# Ada_-_small_square_incomplete.net
KiCad netlist of a schematic drawn in EasyEDA Pro
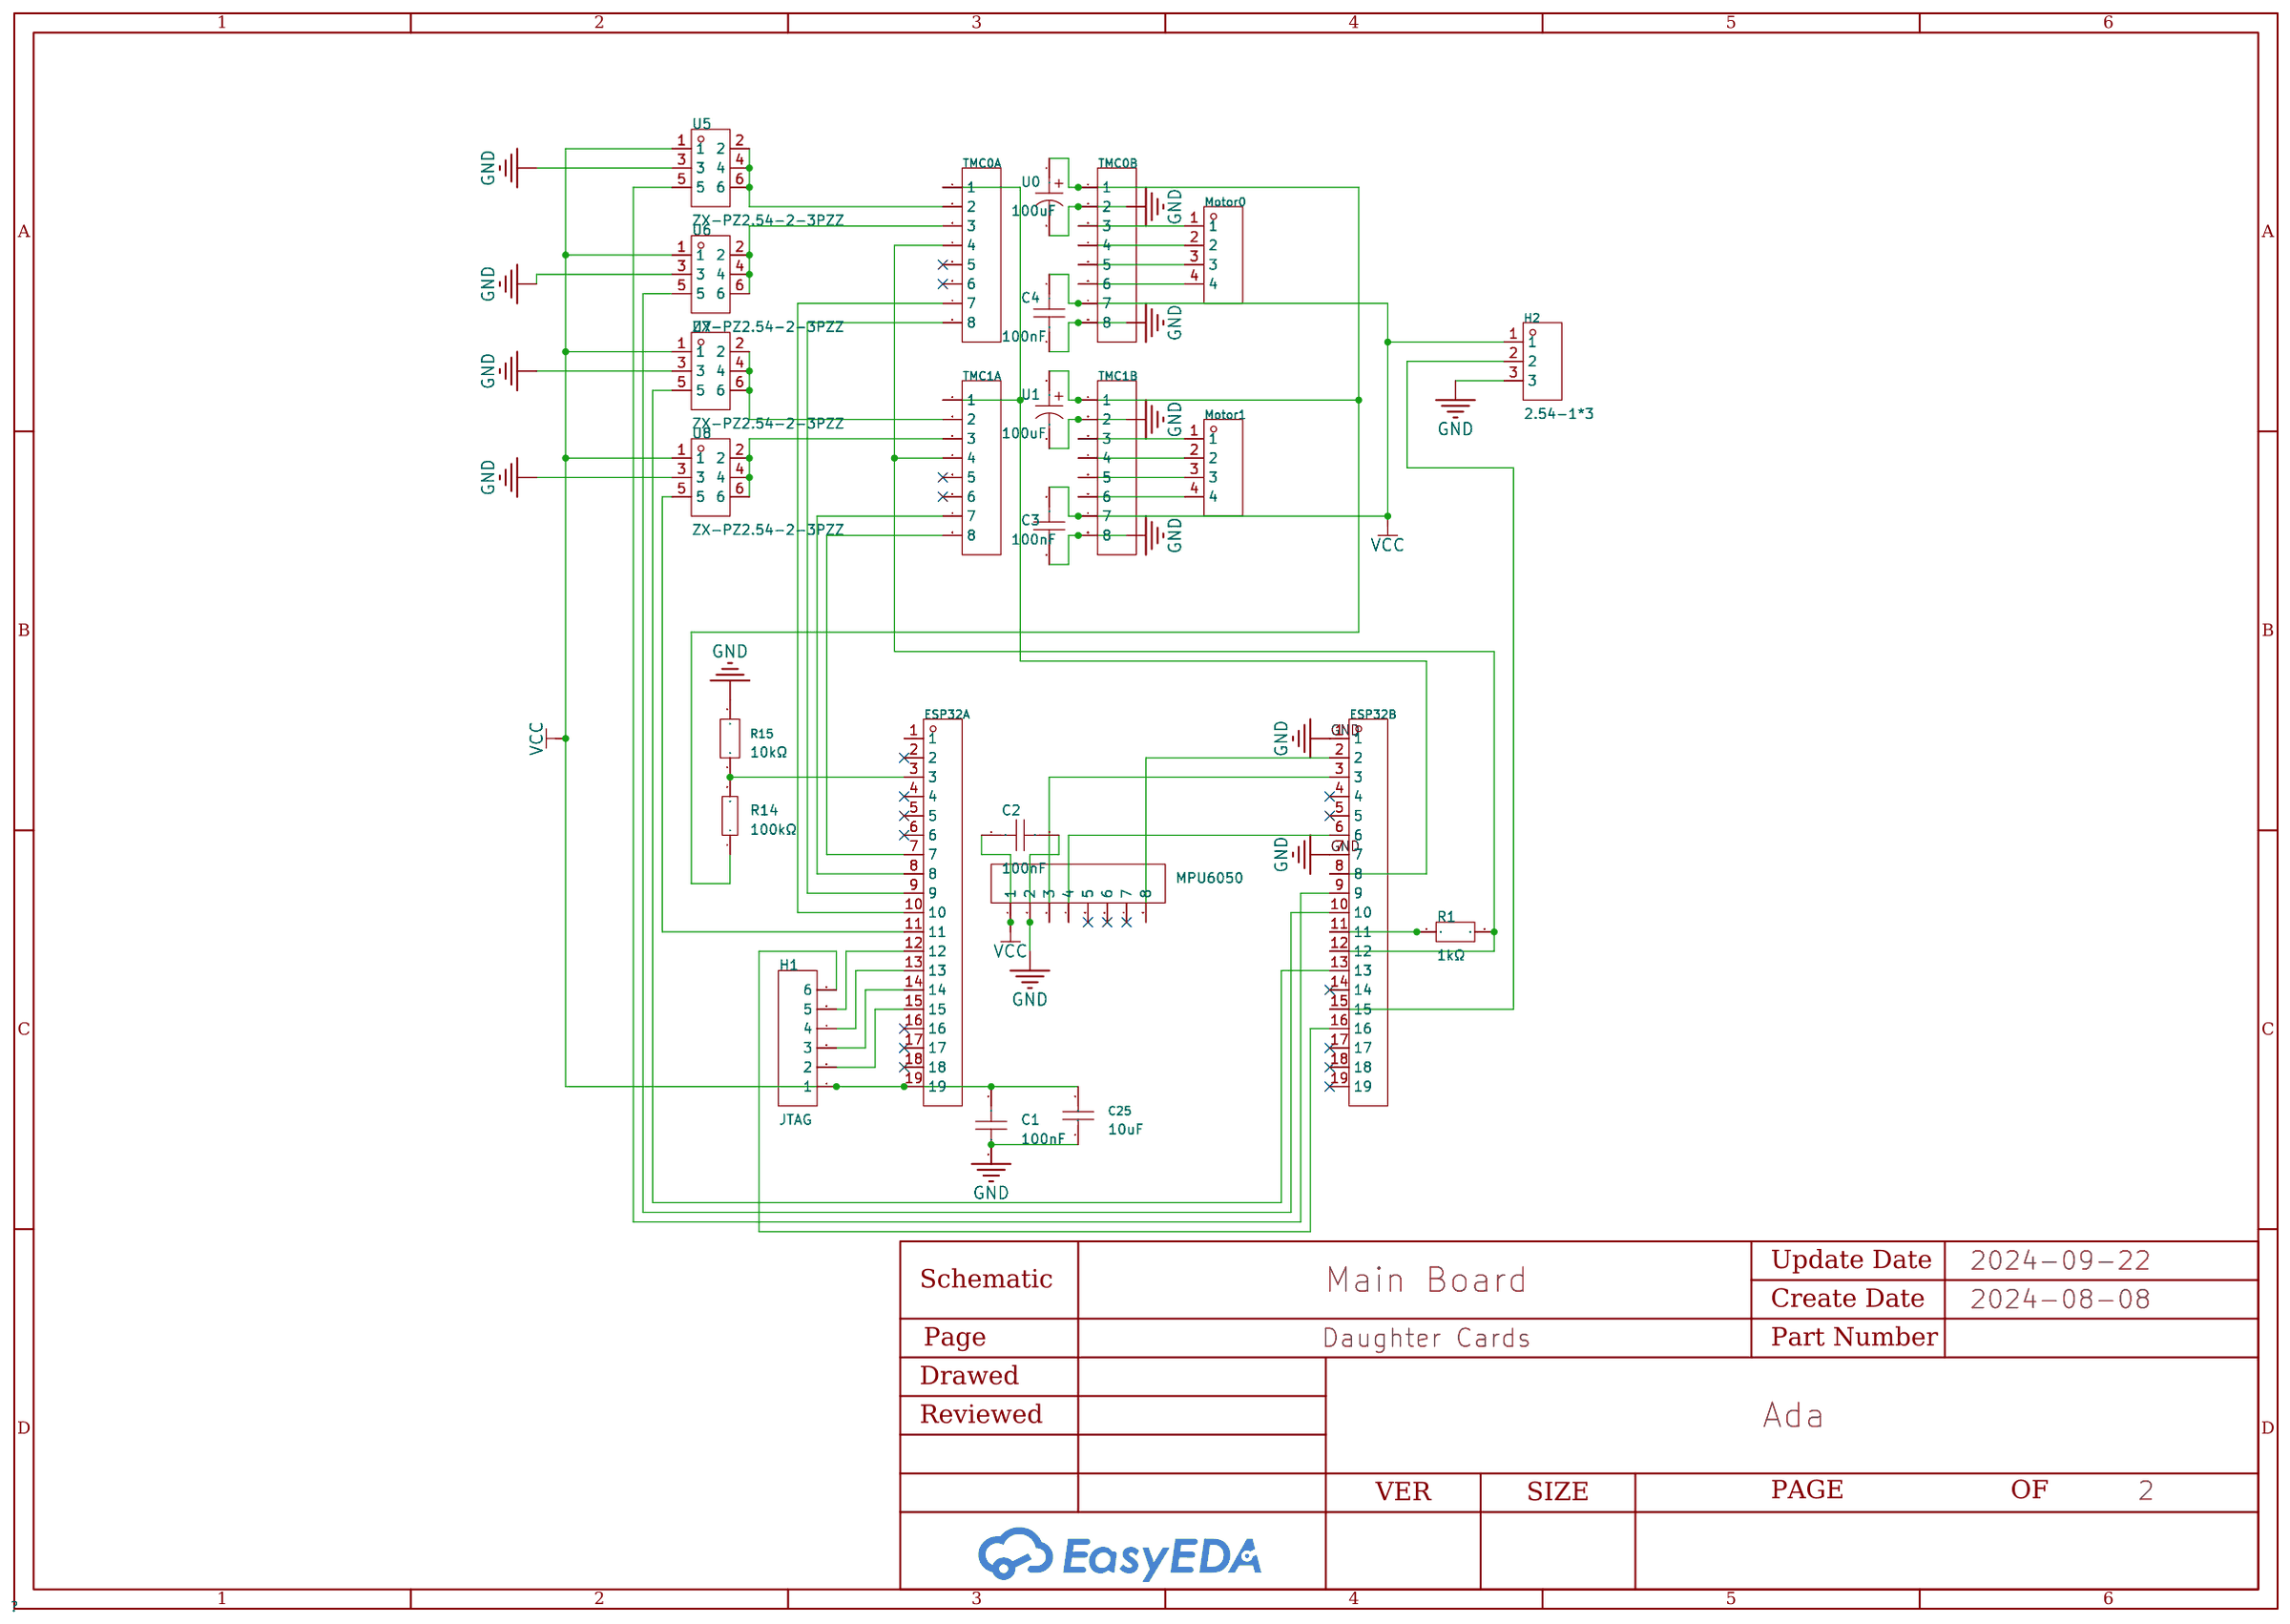
[diagram p0: Daughter Cards]
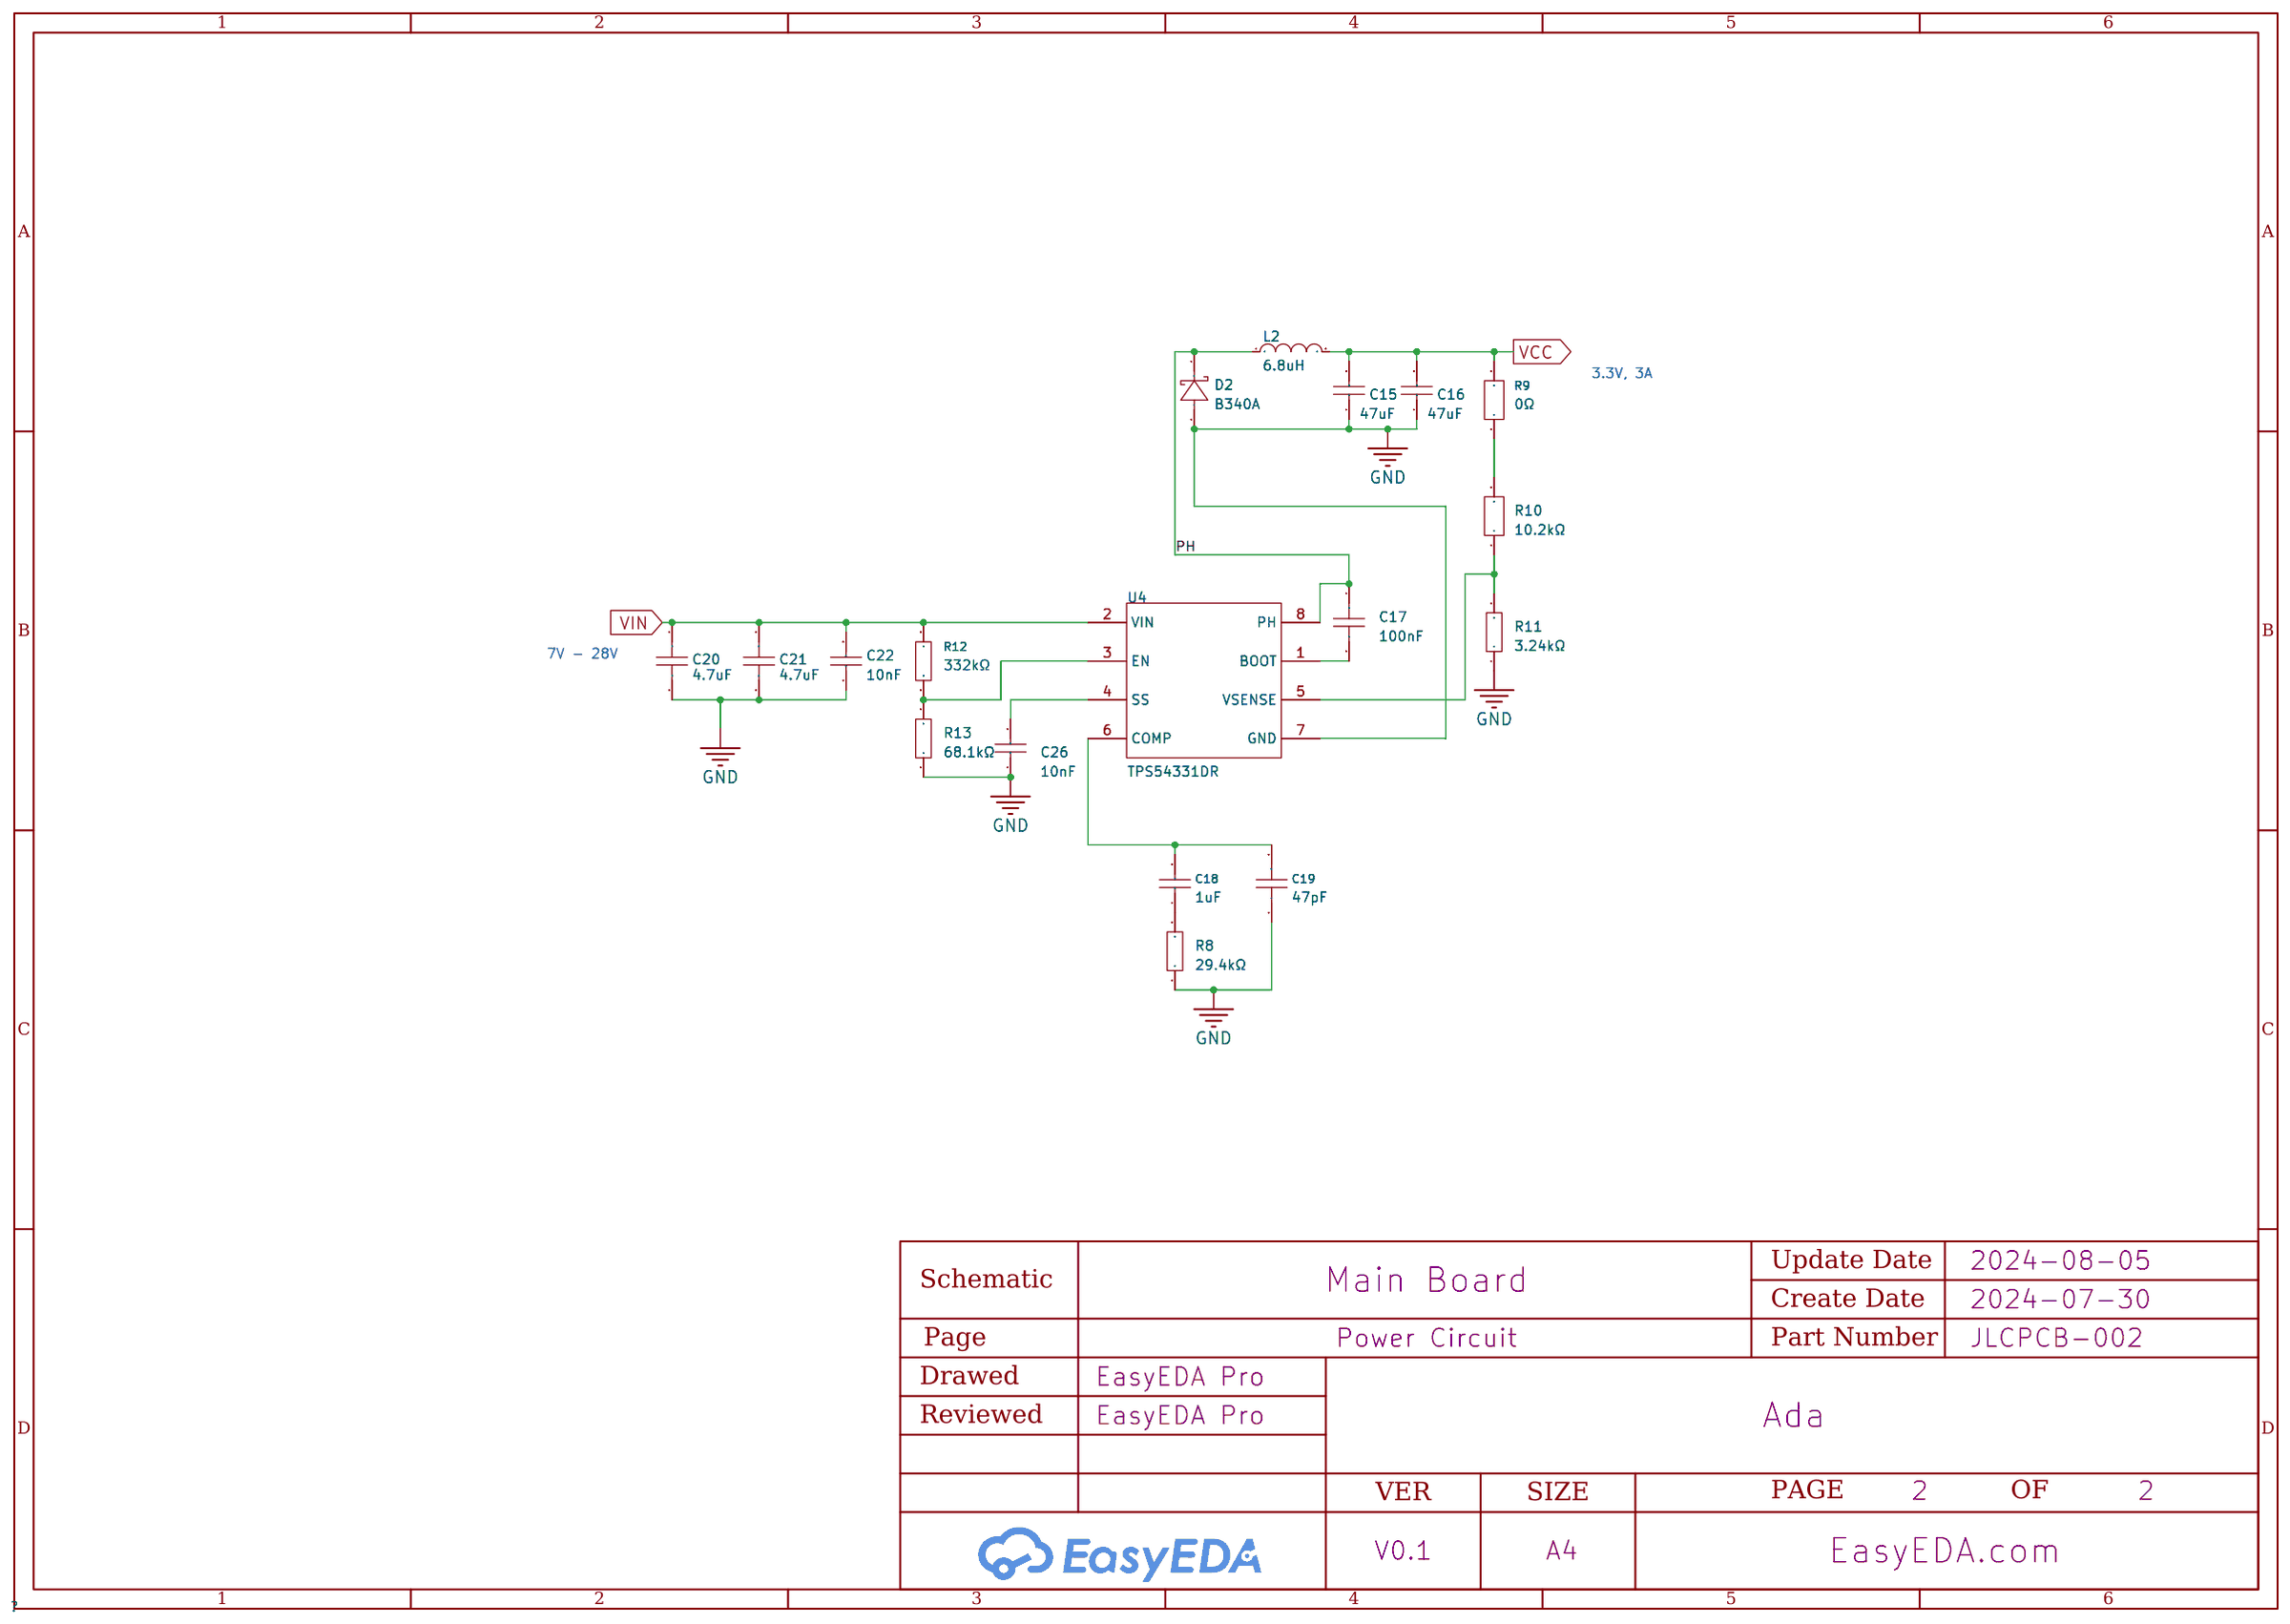
[diagram p1: Power Circuit]

(export (version "E")
  (design (tool "Eeschema 10.0.6"))
  (components
    (comp (ref "C1")
      (value "100nF")
      (footprint "easyedapro:C0201")
      (fields
        (field (name "Manufacturer Part") "CL03A104KQ3NNNC")
        (field (name "Manufacturer") "SAMSUNG(三星)")
      )
      (libsource (lib "easyedapro") (part "CL03A104KQ3NNNC"))
    )
    (comp (ref "C2")
      (value "100nF")
      (footprint "easyedapro:C0201")
      (fields
        (field (name "Manufacturer Part") "CL03A104KQ3NNNC")
        (field (name "Manufacturer") "SAMSUNG(三星)")
      )
      (libsource (lib "easyedapro") (part "CL03A104KQ3NNNC"))
    )
    (comp (ref "C3")
      (value "100nF")
      (footprint "easyedapro:C0201")
      (fields
        (field (name "Manufacturer Part") "CL03A104KQ3NNNC")
        (field (name "Manufacturer") "SAMSUNG(三星)")
      )
      (libsource (lib "easyedapro") (part "CL03A104KQ3NNNC"))
    )
    (comp (ref "C4")
      (value "100nF")
      (footprint "easyedapro:C0201")
      (fields
        (field (name "Manufacturer Part") "CL03A104KQ3NNNC")
        (field (name "Manufacturer") "SAMSUNG(三星)")
      )
      (libsource (lib "easyedapro") (part "CL03A104KQ3NNNC"))
    )
    (comp (ref "C25")
      (value "10uF")
      (footprint "easyedapro:C0402")
      (fields
        (field (name "Manufacturer Part") "CL05A106MQ5NUNC")
        (field (name "Manufacturer") "SAMSUNG(三星)")
      )
      (libsource (lib "easyedapro") (part "CL05A106MQ5NUNC"))
    )
    (comp (ref "ESP32A")
      (value "ESP32")
      (footprint "easyedapro:HDR-TH_19P-P2.54-V-F")
      (fields (field (name "Manufacturer Part") "2.54-1*19P母") (field (name "Manufacturer") "BOOMELE(博穆精密)"))
      (libsource (lib "easyedapro") (part "2.54-1*19P母"))
    )
    (comp (ref "ESP32B")
      (value "2.54-1*19P母")
      (footprint "easyedapro:HDR-TH_19P-P2.54-V-F")
      (fields (field (name "Manufacturer") "BOOMELE(博穆精密)"))
      (libsource (lib "easyedapro") (part "2.54-1*19P母"))
    )
    (comp (ref "H1")
      (value "JTAG")
      (footprint "easyedapro:HDR-TH_6P-P2.54-V-M-1")
      (fields (field (name "Manufacturer Part") "2.54-1x6P直针") (field (name "Manufacturer") "BOOMELE(博穆精密)"))
      (libsource (lib "easyedapro") (part "Header-Male-2.54_1x6"))
    )
    (comp (ref "H2")
      (value "2.54-1*3")
      (footprint "easyedapro:HDR-TH_3P-P2.54-V-M-1")
      (description "Pin Structure:1x3P Pitch:2.54mm Number of Rows:Plugin Number of Pins:3P Contact Plating:Gold")
      (fields (field (name "Manufacturer") "ZHOURI(洲日)"))
      (libsource (lib "easyedapro") (part "2.54-1*3"))
    )
    (comp (ref "Motor0")
      (value "Motor 0")
      (footprint "easyedapro:HDR-TH_4P-P2.54-V-M")
      (fields (field (name "Manufacturer Part") "PZ254V-11-04P") (field (name "Manufacturer") "XFCN(兴飞)"))
      (libsource (lib "easyedapro") (part "PZ254V-11-04P_C2691448"))
    )
    (comp (ref "Motor1")
      (value "Motor 1")
      (footprint "easyedapro:HDR-TH_4P-P2.54-V-M")
      (fields (field (name "Manufacturer Part") "PZ254V-11-04P") (field (name "Manufacturer") "XFCN(兴飞)"))
      (libsource (lib "easyedapro") (part "PZ254V-11-04P_C2691448"))
    )
    (comp (ref "MPU6050")
      (value "MPU6050")
      (footprint "easyedapro:HDR-TH_8P-P2.54-V-F-1")
      (fields (field (name "Manufacturer Part") "2.54-1*8P母环保") (field (name "Manufacturer") "BOOMELE(博穆精密)"))
      (libsource (lib "easyedapro") (part "Header-Female-2.54_1x8"))
    )
    (comp (ref "R1")
      (value "1kΩ")
      (footprint "easyedapro:R0603")
      (fields (field (name "Manufacturer Part") "FCR0603F1K") (field (name "Manufacturer") "VO(翔胜)"))
      (libsource (lib "easyedapro") (part "FCR0603F1K"))
    )
    (comp (ref "R14")
      (value "100kΩ")
      (footprint "easyedapro:R0201")
      (fields
        (field (name "Manufacturer Part") "0201WMF1003TEE")
        (field (name "Manufacturer") "UNI-ROYAL(厚声)")
      )
      (libsource (lib "easyedapro") (part "0201WMF1003TEE"))
    )
    (comp (ref "R15")
      (value "10kΩ")
      (footprint "easyedapro:R0201")
      (fields
        (field (name "Manufacturer Part") "0201WMF1002TEE")
        (field (name "Manufacturer") "UNI-ROYAL(厚声)")
      )
      (libsource (lib "easyedapro") (part "0201WMF1002TEE"))
    )
    (comp (ref "TMC0A")
      (value "TMC0A")
      (footprint "easyedapro:HDR-TH_8P-P2.54-V-F-1")
      (fields (field (name "Manufacturer Part") "2.54-1*8P母环保") (field (name "Manufacturer") "BOOMELE(博穆精密)"))
      (libsource (lib "easyedapro") (part "Header-Female-2.54_1x8"))
    )
    (comp (ref "TMC0B")
      (value "2.54-1*8P母环保")
      (footprint "easyedapro:HDR-TH_8P-P2.54-V-F-1")
      (fields (field (name "Manufacturer") "BOOMELE(博穆精密)"))
      (libsource (lib "easyedapro") (part "Header-Female-2.54_1x8"))
    )
    (comp (ref "TMC1A")
      (value "TMC2209")
      (footprint "easyedapro:HDR-TH_8P-P2.54-V-F-1")
      (fields (field (name "Manufacturer Part") "2.54-1*8P母环保") (field (name "Manufacturer") "BOOMELE(博穆精密)"))
      (libsource (lib "easyedapro") (part "Header-Female-2.54_1x8"))
    )
    (comp (ref "TMC1B")
      (value "2.54-1*8P母环保")
      (footprint "easyedapro:HDR-TH_8P-P2.54-V-F-1")
      (fields (field (name "Manufacturer") "BOOMELE(博穆精密)"))
      (libsource (lib "easyedapro") (part "Header-Female-2.54_1x8"))
    )
    (comp (ref "U0")
      (value "100uF")
      (footprint "easyedapro:CAP-TH_BD6.3-P2.50-D0.5-FD")
      (fields (field (name "Manufacturer Part") "03EC0728") (field (name "Manufacturer") "KNSCHA(科尼盛)"))
      (libsource (lib "easyedapro") (part "03EC0728"))
    )
    (comp (ref "U1")
      (value "100uF")
      (footprint "easyedapro:CAP-TH_BD6.3-P2.50-D0.5-FD")
      (fields (field (name "Manufacturer Part") "03EC0728") (field (name "Manufacturer") "KNSCHA(科尼盛)"))
      (libsource (lib "easyedapro") (part "03EC0728"))
    )
    (comp (ref "U5")
      (value "ZX-PZ2.54-2-3PZZ")
      (footprint "easyedapro:HDR-TH_6P-P2.54-V-M-R2-C3-S2.54-1")
      (fields (field (name "Manufacturer") "Megastar(兆星)"))
      (libsource (lib "easyedapro") (part "ZX-PZ2.54-2-3PZZ"))
    )
    (comp (ref "U6")
      (value "ZX-PZ2.54-2-3PZZ")
      (footprint "easyedapro:HDR-TH_6P-P2.54-V-M-R2-C3-S2.54-1")
      (fields (field (name "Manufacturer") "Megastar(兆星)"))
      (libsource (lib "easyedapro") (part "ZX-PZ2.54-2-3PZZ"))
    )
    (comp (ref "U7")
      (value "ZX-PZ2.54-2-3PZZ")
      (footprint "easyedapro:HDR-TH_6P-P2.54-V-M-R2-C3-S2.54-1")
      (fields (field (name "Manufacturer") "Megastar(兆星)"))
      (libsource (lib "easyedapro") (part "ZX-PZ2.54-2-3PZZ"))
    )
    (comp (ref "U8")
      (value "ZX-PZ2.54-2-3PZZ")
      (footprint "easyedapro:HDR-TH_6P-P2.54-V-M-R2-C3-S2.54-1")
      (fields (field (name "Manufacturer") "Megastar(兆星)"))
      (libsource (lib "easyedapro") (part "ZX-PZ2.54-2-3PZZ"))
    )
    (comp (ref "C15")
      (value "47uF")
      (footprint "easyedapro:C0805")
      (fields
        (field (name "Manufacturer Part") "CL21A476MQYNNNE")
        (field (name "Manufacturer") "SAMSUNG(三星)")
      )
      (libsource (lib "easyedapro") (part "CL21A476MQYNNNE"))
    )
    (comp (ref "C16")
      (value "47uF")
      (footprint "easyedapro:C0805")
      (fields
        (field (name "Manufacturer Part") "CL21A476MQYNNNE")
        (field (name "Manufacturer") "SAMSUNG(三星)")
      )
      (libsource (lib "easyedapro") (part "CL21A476MQYNNNE"))
    )
    (comp (ref "C17")
      (value "100nF")
      (footprint "easyedapro:C0201")
      (fields
        (field (name "Manufacturer Part") "CL03A104KQ3NNNC")
        (field (name "Manufacturer") "SAMSUNG(三星)")
      )
      (libsource (lib "easyedapro") (part "CL03A104KQ3NNNC"))
    )
    (comp (ref "C18")
      (value "1uF")
      (footprint "easyedapro:C0402")
      (fields
        (field (name "Manufacturer Part") "CL05A105KQ5NNNC")
        (field (name "Manufacturer") "SAMSUNG(三星)")
      )
      (libsource (lib "easyedapro") (part "CL05A105KQ5NNNC"))
    )
    (comp (ref "C19")
      (value "47pF")
      (footprint "easyedapro:C0603")
      (fields
        (field (name "Manufacturer Part") "CC0603JRNPO8BN470")
        (field (name "Manufacturer") "YAGEO(国巨)")
      )
      (libsource (lib "easyedapro") (part "CC0603JRNPO8BN470"))
    )
    (comp (ref "C20")
      (value "4.7uF")
      (footprint "easyedapro:C0603")
      (fields
        (field (name "Manufacturer Part") "CL10A475KL8NRNC")
        (field (name "Manufacturer") "SAMSUNG(三星)")
      )
      (libsource (lib "easyedapro") (part "CL10A475KL8NRNC"))
    )
    (comp (ref "C21")
      (value "4.7uF")
      (footprint "easyedapro:C0603")
      (fields
        (field (name "Manufacturer Part") "CL10A475KL8NRNC")
        (field (name "Manufacturer") "SAMSUNG(三星)")
      )
      (libsource (lib "easyedapro") (part "CL10A475KL8NRNC"))
    )
    (comp (ref "C22")
      (value "10nF")
      (footprint "easyedapro:C0603")
      (fields
        (field (name "Manufacturer Part") "CL10B103KB8NNNC")
        (field (name "Manufacturer") "SAMSUNG(三星)")
      )
      (libsource (lib "easyedapro") (part "CL10B103KB8NNNC"))
    )
    (comp (ref "C26")
      (value "10nF")
      (footprint "easyedapro:C0201")
      (fields
        (field (name "Manufacturer Part") "GRM033R70J103KA01D")
        (field (name "Manufacturer") "muRata(村田)")
      )
      (libsource (lib "easyedapro") (part "GRM033R70J103KA01D"))
    )
    (comp (ref "D2")
      (value "B340A")
      (footprint "easyedapro:SMA_L4.3-W2.6-LS5.0-RD")
      (fields (field (name "Manufacturer") "FUXINSEMI(富芯森美)"))
      (libsource (lib "easyedapro") (part "B340A_C3018525"))
    )
    (comp (ref "L2")
      (value "6.8uH")
      (footprint "easyedapro:IND-SMD_L5.2-W5.2_MS0530-XX")
      (fields (field (name "Manufacturer Part") "MDA5030-6R8M") (field (name "Manufacturer") "KOHERelec(科或)"))
      (libsource (lib "easyedapro") (part "MDA5030-6R8M"))
    )
    (comp (ref "R8")
      (value "29.4kΩ")
      (footprint "easyedapro:R0201")
      (fields (field (name "Manufacturer Part") "RC-01W2942FT") (field (name "Manufacturer") "FH(风华)"))
      (libsource (lib "easyedapro") (part "RC-01W2942FT"))
    )
    (comp (ref "R9")
      (value "0Ω")
      (footprint "easyedapro:R0201")
      (fields
        (field (name "Manufacturer Part") "0201WMF0000TEE")
        (field (name "Manufacturer") "UNI-ROYAL(厚声)")
      )
      (libsource (lib "easyedapro") (part "0201WMF0000TEE"))
    )
    (comp (ref "R10")
      (value "10.2kΩ")
      (footprint "easyedapro:R0201")
      (fields (field (name "Manufacturer Part") "RTT011022FTH") (field (name "Manufacturer") "RALEC(旺诠)"))
      (libsource (lib "easyedapro") (part "RTT011022FTH"))
    )
    (comp (ref "R11")
      (value "3.24kΩ")
      (footprint "easyedapro:R0603")
      (fields
        (field (name "Manufacturer Part") "0603WAF3241T5E")
        (field (name "Manufacturer") "UNI-ROYAL(厚声)")
      )
      (libsource (lib "easyedapro") (part "0603WAF3241T5E"))
    )
    (comp (ref "R12")
      (value "332kΩ")
      (footprint "easyedapro:R0402")
      (fields
        (field (name "Manufacturer Part") "0402WGF3323TCE")
        (field (name "Manufacturer") "UNI-ROYAL(厚声)")
      )
      (libsource (lib "easyedapro") (part "0402WGF3323TCE"))
    )
    (comp (ref "R13")
      (value "68.1kΩ")
      (footprint "easyedapro:R0402")
      (fields (field (name "Manufacturer Part") "AC0402FR-0768K1L") (field (name "Manufacturer") "YAGEO(国巨)"))
      (libsource (lib "easyedapro") (part "AC0402FR-0768K1L"))
    )
    (comp (ref "U4")
      (value "TPS54331DR")
      (footprint "easyedapro:SOIC-8_L5.0-W4.0-P1.27-LS6.0-BL")
      (fields (field (name "Manufacturer") "TI(德州仪器)"))
      (libsource (lib "easyedapro") (part "TPS54331DR"))
    )
  )
  (nets
    (net (code "1") (name "GND") (class "Default")
      (node (ref "C1") (pin "2") (pinfunction "2_2") (pintype "unspecified"))
      (node (ref "C15") (pin "1") (pinfunction "1_1") (pintype "input"))
      (node (ref "C16") (pin "1") (pinfunction "1_1") (pintype "input"))
      (node (ref "C19") (pin "1") (pinfunction "1_1") (pintype "input"))
      (node (ref "C2") (pin "2") (pinfunction "2_2") (pintype "unspecified"))
      (node (ref "C20") (pin "2") (pinfunction "2_2") (pintype "unspecified"))
      (node (ref "C21") (pin "2") (pinfunction "2_2") (pintype "unspecified"))
      (node (ref "C22") (pin "1") (pinfunction "1_1") (pintype "input"))
      (node (ref "C25") (pin "1") (pinfunction "1_1") (pintype "input"))
      (node (ref "C26") (pin "1") (pinfunction "1_1") (pintype "input"))
      (node (ref "C3") (pin "2") (pinfunction "2_2") (pintype "unspecified"))
      (node (ref "C4") (pin "2") (pinfunction "2_2") (pintype "unspecified"))
      (node (ref "D2") (pin "2") (pinfunction "A_2") (pintype "unspecified"))
      (node (ref "ESP32B") (pin "1") (pinfunction "1_1") (pintype "input"))
      (node (ref "ESP32B") (pin "7") (pinfunction "7_7") (pintype "input"))
      (node (ref "H2") (pin "3") (pinfunction "3_3") (pintype "input"))
      (node (ref "MPU6050") (pin "2") (pinfunction "2_2") (pintype "input"))
      (node (ref "R11") (pin "1") (pinfunction "1_1") (pintype "input"))
      (node (ref "R13") (pin "1") (pinfunction "1_1") (pintype "unspecified"))
      (node (ref "R15") (pin "2") (pinfunction "2_2") (pintype "input"))
      (node (ref "R8") (pin "1") (pinfunction "1_1") (pintype "unspecified"))
      (node (ref "TMC0B") (pin "2") (pinfunction "2_2") (pintype "input"))
      (node (ref "TMC0B") (pin "8") (pinfunction "8_8") (pintype "input"))
      (node (ref "TMC1B") (pin "2") (pinfunction "2_2") (pintype "input"))
      (node (ref "TMC1B") (pin "8") (pinfunction "8_8") (pintype "input"))
      (node (ref "U0") (pin "2") (pinfunction "2_2") (pintype "input"))
      (node (ref "U1") (pin "2") (pinfunction "2_2") (pintype "input"))
      (node (ref "U4") (pin "7") (pinfunction "GND_7") (pintype "unspecified"))
      (node (ref "U5") (pin "3") (pinfunction "3_3") (pintype "unspecified"))
      (node (ref "U6") (pin "3") (pinfunction "3_3") (pintype "unspecified"))
      (node (ref "U7") (pin "3") (pinfunction "3_3") (pintype "unspecified"))
      (node (ref "U8") (pin "3") (pinfunction "3_3") (pintype "unspecified"))
    )
    (net (code "2") (name "Net-(C18-Pad1)") (class "Default")
      (node (ref "C18") (pin "1") (pinfunction "1_1") (pintype "input"))
      (node (ref "R8") (pin "2") (pinfunction "2_2") (pintype "unspecified"))
    )
    (net (code "3") (name "Net-(ESP32A-Pad3)") (class "Default")
      (node (ref "ESP32A") (pin "3") (pinfunction "3_3") (pintype "input"))
      (node (ref "R14") (pin "2") (pinfunction "2_2") (pintype "unspecified"))
      (node (ref "R15") (pin "1") (pinfunction "1_1") (pintype "input"))
    )
    (net (code "4") (name "Net-(ESP32A-Pad7)") (class "Default")
      (node (ref "ESP32A") (pin "7") (pinfunction "7_7") (pintype "input"))
      (node (ref "TMC1A") (pin "8") (pinfunction "8_8") (pintype "input"))
    )
    (net (code "5") (name "Net-(ESP32A-Pad8)") (class "Default")
      (node (ref "ESP32A") (pin "8") (pinfunction "8_8") (pintype "input"))
      (node (ref "TMC1A") (pin "7") (pinfunction "7_7") (pintype "input"))
    )
    (net (code "6") (name "Net-(ESP32A-Pad9)") (class "Default")
      (node (ref "ESP32A") (pin "9") (pinfunction "9_9") (pintype "input"))
      (node (ref "TMC0A") (pin "8") (pinfunction "8_8") (pintype "input"))
    )
    (net (code "7") (name "Net-(ESP32A-Pad10)") (class "Default")
      (node (ref "ESP32A") (pin "10") (pinfunction "10_10") (pintype "input"))
      (node (ref "TMC0A") (pin "7") (pinfunction "7_7") (pintype "input"))
    )
    (net (code "8") (name "Net-(ESP32A-Pad11)") (class "Default")
      (node (ref "ESP32A") (pin "11") (pinfunction "11_11") (pintype "input"))
      (node (ref "U8") (pin "5") (pinfunction "5_5") (pintype "unspecified"))
    )
    (net (code "9") (name "Net-(ESP32A-Pad12)") (class "Default")
      (node (ref "ESP32A") (pin "12") (pinfunction "12_12") (pintype "input"))
      (node (ref "H1") (pin "5") (pinfunction "5_5") (pintype "input"))
    )
    (net (code "10") (name "Net-(ESP32A-Pad13)") (class "Default")
      (node (ref "ESP32A") (pin "13") (pinfunction "13_13") (pintype "input"))
      (node (ref "H1") (pin "4") (pinfunction "4_4") (pintype "input"))
    )
    (net (code "11") (name "Net-(ESP32A-Pad14)") (class "Default")
      (node (ref "ESP32A") (pin "14") (pinfunction "14_14") (pintype "input"))
      (node (ref "H1") (pin "3") (pinfunction "3_3") (pintype "input"))
    )
    (net (code "12") (name "Net-(ESP32A-Pad15)") (class "Default")
      (node (ref "ESP32A") (pin "15") (pinfunction "15_15") (pintype "input"))
      (node (ref "H1") (pin "2") (pinfunction "2_2") (pintype "input"))
    )
    (net (code "13") (name "Net-(ESP32B-Pad2)") (class "Default")
      (node (ref "ESP32B") (pin "2") (pinfunction "2_2") (pintype "input"))
      (node (ref "MPU6050") (pin "8") (pinfunction "8_8") (pintype "input"))
    )
    (net (code "14") (name "Net-(ESP32B-Pad3)") (class "Default")
      (node (ref "ESP32B") (pin "3") (pinfunction "3_3") (pintype "input"))
      (node (ref "MPU6050") (pin "3") (pinfunction "3_3") (pintype "input"))
    )
    (net (code "15") (name "Net-(ESP32B-Pad6)") (class "Default")
      (node (ref "ESP32B") (pin "6") (pinfunction "6_6") (pintype "input"))
      (node (ref "MPU6050") (pin "4") (pinfunction "4_4") (pintype "input"))
    )
    (net (code "16") (name "Net-(ESP32B-Pad8)") (class "Default")
      (node (ref "ESP32B") (pin "8") (pinfunction "8_8") (pintype "input"))
      (node (ref "TMC0A") (pin "1") (pinfunction "1_1") (pintype "input"))
      (node (ref "TMC1A") (pin "1") (pinfunction "1_1") (pintype "input"))
    )
    (net (code "17") (name "Net-(ESP32B-Pad9)") (class "Default")
      (node (ref "ESP32B") (pin "9") (pinfunction "9_9") (pintype "input"))
      (node (ref "U5") (pin "5") (pinfunction "5_5") (pintype "unspecified"))
    )
    (net (code "18") (name "Net-(ESP32B-Pad10)") (class "Default")
      (node (ref "ESP32B") (pin "10") (pinfunction "10_10") (pintype "input"))
      (node (ref "U6") (pin "5") (pinfunction "5_5") (pintype "unspecified"))
    )
    (net (code "19") (name "Net-(ESP32B-Pad11)") (class "Default")
      (node (ref "ESP32B") (pin "11") (pinfunction "11_11") (pintype "input"))
      (node (ref "R1") (pin "1") (pinfunction "1_1") (pintype "unspecified"))
    )
    (net (code "20") (name "Net-(ESP32B-Pad12)") (class "Default")
      (node (ref "ESP32B") (pin "12") (pinfunction "12_12") (pintype "input"))
      (node (ref "R1") (pin "2") (pinfunction "2_2") (pintype "unspecified"))
      (node (ref "TMC0A") (pin "4") (pinfunction "4_4") (pintype "input"))
      (node (ref "TMC1A") (pin "4") (pinfunction "4_4") (pintype "input"))
    )
    (net (code "21") (name "Net-(ESP32B-Pad13)") (class "Default")
      (node (ref "ESP32B") (pin "13") (pinfunction "13_13") (pintype "input"))
      (node (ref "U7") (pin "5") (pinfunction "5_5") (pintype "unspecified"))
    )
    (net (code "22") (name "Net-(ESP32B-Pad15)") (class "Default")
      (node (ref "ESP32B") (pin "15") (pinfunction "15_15") (pintype "input"))
      (node (ref "H2") (pin "2") (pinfunction "2_2") (pintype "input"))
    )
    (net (code "23") (name "Net-(ESP32B-Pad16)") (class "Default")
      (node (ref "ESP32B") (pin "16") (pinfunction "16_16") (pintype "input"))
      (node (ref "H1") (pin "6") (pinfunction "6_6") (pintype "input"))
    )
    (net (code "24") (name "Net-(Motor0-Pad1)") (class "Default")
      (node (ref "Motor0") (pin "1") (pinfunction "1_1") (pintype "input"))
      (node (ref "TMC0B") (pin "3") (pinfunction "3_3") (pintype "input"))
    )
    (net (code "25") (name "Net-(Motor0-Pad2)") (class "Default")
      (node (ref "Motor0") (pin "2") (pinfunction "2_2") (pintype "input"))
      (node (ref "TMC0B") (pin "4") (pinfunction "4_4") (pintype "input"))
    )
    (net (code "26") (name "Net-(Motor0-Pad3)") (class "Default")
      (node (ref "Motor0") (pin "3") (pinfunction "3_3") (pintype "input"))
      (node (ref "TMC0B") (pin "5") (pinfunction "5_5") (pintype "input"))
    )
    (net (code "27") (name "Net-(Motor0-Pad4)") (class "Default")
      (node (ref "Motor0") (pin "4") (pinfunction "4_4") (pintype "input"))
      (node (ref "TMC0B") (pin "6") (pinfunction "6_6") (pintype "input"))
    )
    (net (code "28") (name "Net-(Motor1-Pad1)") (class "Default")
      (node (ref "Motor1") (pin "1") (pinfunction "1_1") (pintype "input"))
      (node (ref "TMC1B") (pin "3") (pinfunction "3_3") (pintype "input"))
    )
    (net (code "29") (name "Net-(Motor1-Pad2)") (class "Default")
      (node (ref "Motor1") (pin "2") (pinfunction "2_2") (pintype "input"))
      (node (ref "TMC1B") (pin "4") (pinfunction "4_4") (pintype "input"))
    )
    (net (code "30") (name "Net-(Motor1-Pad3)") (class "Default")
      (node (ref "Motor1") (pin "3") (pinfunction "3_3") (pintype "input"))
      (node (ref "TMC1B") (pin "5") (pinfunction "5_5") (pintype "input"))
    )
    (net (code "31") (name "Net-(Motor1-Pad4)") (class "Default")
      (node (ref "Motor1") (pin "4") (pinfunction "4_4") (pintype "input"))
      (node (ref "TMC1B") (pin "6") (pinfunction "6_6") (pintype "input"))
    )
    (net (code "32") (name "Net-(R10-Pad2)") (class "Default")
      (node (ref "R10") (pin "2") (pinfunction "2_2") (pintype "unspecified"))
      (node (ref "R9") (pin "1") (pinfunction "1_1") (pintype "input"))
    )
    (net (code "33") (name "Net-(R14-Pad1)") (class "Default")
      (node (ref "R14") (pin "1") (pinfunction "1_1") (pintype "unspecified"))
      (node (ref "TMC0B") (pin "1") (pinfunction "1_1") (pintype "input"))
      (node (ref "TMC1B") (pin "1") (pinfunction "1_1") (pintype "input"))
      (node (ref "U0") (pin "1") (pinfunction "1_1") (pintype "input"))
      (node (ref "U1") (pin "1") (pinfunction "1_1") (pintype "input"))
    )
    (net (code "34") (name "Net-(TMC0A-Pad2)") (class "Default")
      (node (ref "TMC0A") (pin "2") (pinfunction "2_2") (pintype "input"))
      (node (ref "U5") (pin "2") (pinfunction "2_2") (pintype "unspecified"))
      (node (ref "U5") (pin "4") (pinfunction "4_4") (pintype "unspecified"))
      (node (ref "U5") (pin "6") (pinfunction "6_6") (pintype "unspecified"))
    )
    (net (code "35") (name "Net-(TMC0A-Pad3)") (class "Default")
      (node (ref "TMC0A") (pin "3") (pinfunction "3_3") (pintype "input"))
      (node (ref "U6") (pin "2") (pinfunction "2_2") (pintype "unspecified"))
      (node (ref "U6") (pin "4") (pinfunction "4_4") (pintype "unspecified"))
      (node (ref "U6") (pin "6") (pinfunction "6_6") (pintype "unspecified"))
    )
    (net (code "36") (name "Net-(TMC1A-Pad2)") (class "Default")
      (node (ref "TMC1A") (pin "2") (pinfunction "2_2") (pintype "input"))
      (node (ref "U7") (pin "2") (pinfunction "2_2") (pintype "unspecified"))
      (node (ref "U7") (pin "4") (pinfunction "4_4") (pintype "unspecified"))
      (node (ref "U7") (pin "6") (pinfunction "6_6") (pintype "unspecified"))
    )
    (net (code "37") (name "Net-(TMC1A-Pad3)") (class "Default")
      (node (ref "TMC1A") (pin "3") (pinfunction "3_3") (pintype "input"))
      (node (ref "U8") (pin "2") (pinfunction "2_2") (pintype "unspecified"))
      (node (ref "U8") (pin "4") (pinfunction "4_4") (pintype "unspecified"))
      (node (ref "U8") (pin "6") (pinfunction "6_6") (pintype "unspecified"))
    )
    (net (code "38") (name "Net-(U4-BOOT)") (class "Default")
      (node (ref "C17") (pin "2") (pinfunction "2_2") (pintype "unspecified"))
      (node (ref "U4") (pin "1") (pinfunction "BOOT_1") (pintype "unspecified"))
    )
    (net (code "39") (name "Net-(U4-COMP)") (class "Default")
      (node (ref "C18") (pin "2") (pinfunction "2_2") (pintype "input"))
      (node (ref "C19") (pin "2") (pinfunction "2_2") (pintype "input"))
      (node (ref "U4") (pin "6") (pinfunction "COMP_6") (pintype "unspecified"))
    )
    (net (code "40") (name "Net-(U4-EN)") (class "Default")
      (node (ref "R12") (pin "1") (pinfunction "1_1") (pintype "input"))
      (node (ref "R13") (pin "2") (pinfunction "2_2") (pintype "unspecified"))
      (node (ref "U4") (pin "3") (pinfunction "EN_3") (pintype "unspecified"))
    )
    (net (code "41") (name "Net-(U4-SS)") (class "Default")
      (node (ref "C26") (pin "2") (pinfunction "2_2") (pintype "input"))
      (node (ref "U4") (pin "4") (pinfunction "SS_4") (pintype "unspecified"))
    )
    (net (code "42") (name "Net-(U4-VSENSE)") (class "Default")
      (node (ref "R10") (pin "1") (pinfunction "1_1") (pintype "unspecified"))
      (node (ref "R11") (pin "2") (pinfunction "2_2") (pintype "input"))
      (node (ref "U4") (pin "5") (pinfunction "VSENSE_5") (pintype "unspecified"))
    )
    (net (code "43") (name "PH") (class "Default")
      (node (ref "C17") (pin "1") (pinfunction "1_1") (pintype "unspecified"))
      (node (ref "D2") (pin "1") (pinfunction "K_1") (pintype "unspecified"))
      (node (ref "L2") (pin "1") (pinfunction "1_1") (pintype "unspecified"))
      (node (ref "U4") (pin "8") (pinfunction "PH_8") (pintype "unspecified"))
    )
    (net (code "44") (name "VCC") (class "Default")
      (node (ref "C1") (pin "1") (pinfunction "1_1") (pintype "unspecified"))
      (node (ref "C15") (pin "2") (pinfunction "2_2") (pintype "input"))
      (node (ref "C16") (pin "2") (pinfunction "2_2") (pintype "input"))
      (node (ref "C2") (pin "1") (pinfunction "1_1") (pintype "unspecified"))
      (node (ref "C25") (pin "2") (pinfunction "2_2") (pintype "input"))
      (node (ref "C3") (pin "1") (pinfunction "1_1") (pintype "unspecified"))
      (node (ref "C4") (pin "1") (pinfunction "1_1") (pintype "unspecified"))
      (node (ref "ESP32A") (pin "19") (pinfunction "19_19") (pintype "input"))
      (node (ref "H1") (pin "1") (pinfunction "1_1") (pintype "input"))
      (node (ref "H2") (pin "1") (pinfunction "1_1") (pintype "input"))
      (node (ref "L2") (pin "2") (pinfunction "2_2") (pintype "unspecified"))
      (node (ref "MPU6050") (pin "1") (pinfunction "1_1") (pintype "input"))
      (node (ref "R9") (pin "2") (pinfunction "2_2") (pintype "input"))
      (node (ref "TMC0B") (pin "7") (pinfunction "7_7") (pintype "input"))
      (node (ref "TMC1B") (pin "7") (pinfunction "7_7") (pintype "input"))
      (node (ref "U5") (pin "1") (pinfunction "1_1") (pintype "unspecified"))
      (node (ref "U6") (pin "1") (pinfunction "1_1") (pintype "unspecified"))
      (node (ref "U7") (pin "1") (pinfunction "1_1") (pintype "unspecified"))
      (node (ref "U8") (pin "1") (pinfunction "1_1") (pintype "unspecified"))
    )
    (net (code "45") (name "VIN") (class "Default")
      (node (ref "C20") (pin "1") (pinfunction "1_1") (pintype "unspecified"))
      (node (ref "C21") (pin "1") (pinfunction "1_1") (pintype "unspecified"))
      (node (ref "C22") (pin "2") (pinfunction "2_2") (pintype "input"))
      (node (ref "R12") (pin "2") (pinfunction "2_2") (pintype "input"))
      (node (ref "U4") (pin "2") (pinfunction "VIN_2") (pintype "unspecified"))
    )
    (net (code "46") (name "unconnected-(ESP32A-Pad1)") (class "Default")
      (node (ref "ESP32A") (pin "1") (pinfunction "1_1") (pintype "input"))
    )
    (net (code "47") (name "unconnected-(ESP32A-Pad2)") (class "Default")
      (node (ref "ESP32A") (pin "2") (pinfunction "2_2") (pintype "input+no_connect"))
    )
    (net (code "48") (name "unconnected-(ESP32A-Pad4)") (class "Default")
      (node (ref "ESP32A") (pin "4") (pinfunction "4_4") (pintype "input+no_connect"))
    )
    (net (code "49") (name "unconnected-(ESP32A-Pad5)") (class "Default")
      (node (ref "ESP32A") (pin "5") (pinfunction "5_5") (pintype "input+no_connect"))
    )
    (net (code "50") (name "unconnected-(ESP32A-Pad6)") (class "Default")
      (node (ref "ESP32A") (pin "6") (pinfunction "6_6") (pintype "input+no_connect"))
    )
    (net (code "51") (name "unconnected-(ESP32A-Pad16)") (class "Default")
      (node (ref "ESP32A") (pin "16") (pinfunction "16_16") (pintype "input+no_connect"))
    )
    (net (code "52") (name "unconnected-(ESP32A-Pad17)") (class "Default")
      (node (ref "ESP32A") (pin "17") (pinfunction "17_17") (pintype "input+no_connect"))
    )
    (net (code "53") (name "unconnected-(ESP32A-Pad18)") (class "Default")
      (node (ref "ESP32A") (pin "18") (pinfunction "18_18") (pintype "input+no_connect"))
    )
    (net (code "54") (name "unconnected-(ESP32B-Pad4)") (class "Default")
      (node (ref "ESP32B") (pin "4") (pinfunction "4_4") (pintype "input+no_connect"))
    )
    (net (code "55") (name "unconnected-(ESP32B-Pad5)") (class "Default")
      (node (ref "ESP32B") (pin "5") (pinfunction "5_5") (pintype "input+no_connect"))
    )
    (net (code "56") (name "unconnected-(ESP32B-Pad14)") (class "Default")
      (node (ref "ESP32B") (pin "14") (pinfunction "14_14") (pintype "input+no_connect"))
    )
    (net (code "57") (name "unconnected-(ESP32B-Pad17)") (class "Default")
      (node (ref "ESP32B") (pin "17") (pinfunction "17_17") (pintype "input+no_connect"))
    )
    (net (code "58") (name "unconnected-(ESP32B-Pad18)") (class "Default")
      (node (ref "ESP32B") (pin "18") (pinfunction "18_18") (pintype "input+no_connect"))
    )
    (net (code "59") (name "unconnected-(ESP32B-Pad19)") (class "Default")
      (node (ref "ESP32B") (pin "19") (pinfunction "19_19") (pintype "input+no_connect"))
    )
    (net (code "60") (name "unconnected-(MPU6050-Pad5)") (class "Default")
      (node (ref "MPU6050") (pin "5") (pinfunction "5_5") (pintype "input+no_connect"))
    )
    (net (code "61") (name "unconnected-(MPU6050-Pad6)") (class "Default")
      (node (ref "MPU6050") (pin "6") (pinfunction "6_6") (pintype "input+no_connect"))
    )
    (net (code "62") (name "unconnected-(MPU6050-Pad7)") (class "Default")
      (node (ref "MPU6050") (pin "7") (pinfunction "7_7") (pintype "input+no_connect"))
    )
    (net (code "63") (name "unconnected-(TMC0A-Pad5)") (class "Default")
      (node (ref "TMC0A") (pin "5") (pinfunction "5_5") (pintype "input+no_connect"))
    )
    (net (code "64") (name "unconnected-(TMC0A-Pad6)") (class "Default")
      (node (ref "TMC0A") (pin "6") (pinfunction "6_6") (pintype "input+no_connect"))
    )
    (net (code "65") (name "unconnected-(TMC1A-Pad5)") (class "Default")
      (node (ref "TMC1A") (pin "5") (pinfunction "5_5") (pintype "input+no_connect"))
    )
    (net (code "66") (name "unconnected-(TMC1A-Pad6)") (class "Default")
      (node (ref "TMC1A") (pin "6") (pinfunction "6_6") (pintype "input+no_connect"))
    )
  )
)
